# Buck_scetch.net
KiCad netlist of a schematic drawn in EAGLE
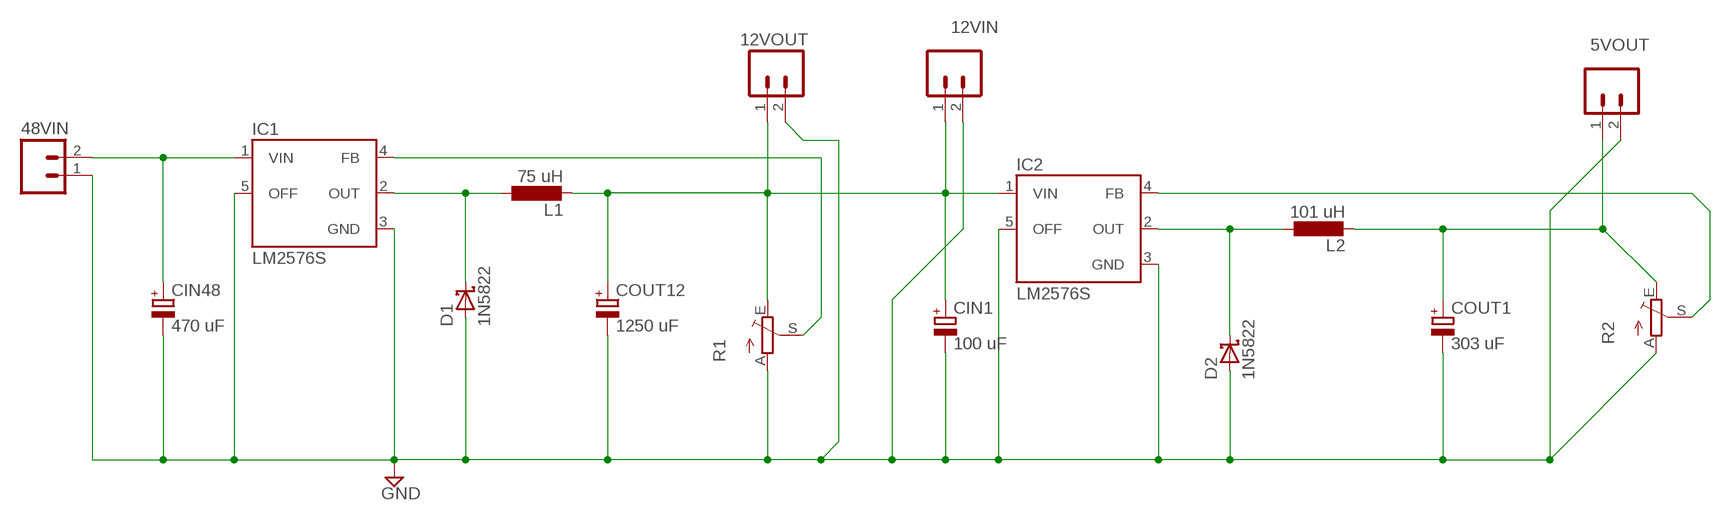
[diagram p0: schematic, sheet 1]

(export (version "E")
  (design (tool "Eeschema 10.0.6"))
  (components
    (comp (ref "5VOUT")
      (value "M02")
      (footprint "eagle-import:02P")
      (libsource (lib "eagle-import") (part "M02"))
    )
    (comp (ref "12VIN")
      (value "M02")
      (footprint "eagle-import:02P")
      (libsource (lib "eagle-import") (part "M02"))
    )
    (comp (ref "12VOUT")
      (value "M02")
      (footprint "eagle-import:02P")
      (libsource (lib "eagle-import") (part "M02"))
    )
    (comp (ref "48VIN")
      (value "M02")
      (footprint "eagle-import:02P")
      (libsource (lib "eagle-import") (part "M02"))
    )
    (comp (ref "CIN1")
      (value "100 uF")
      (footprint "eagle-import:140CLH-0810")
      (libsource (lib "eagle-import") (part "CPOL-EU140CLH-0810"))
    )
    (comp (ref "CIN48")
      (value "470 uF")
      (footprint "eagle-import:140CLH-0810")
      (libsource (lib "eagle-import") (part "CPOL-EU140CLH-0810"))
    )
    (comp (ref "COUT1")
      (value "303 uF")
      (footprint "eagle-import:140CLH-0810")
      (libsource (lib "eagle-import") (part "CPOL-EU140CLH-0810"))
    )
    (comp (ref "COUT12")
      (value "1250 uF")
      (footprint "eagle-import:140CLH-0810")
      (libsource (lib "eagle-import") (part "CPOL-EU140CLH-0810"))
    )
    (comp (ref "D1")
      (value "1N5822")
      (footprint "eagle-import:DIOAD2120W130L950D530P")
      (fields (field (name "MF") "ON Semiconductor"))
      (libsource (lib "eagle-import") (part "1N5822"))
    )
    (comp (ref "D2")
      (value "1N5822")
      (footprint "eagle-import:DIOAD2120W130L950D530P")
      (fields (field (name "MF") "ON Semiconductor"))
      (libsource (lib "eagle-import") (part "1N5822"))
    )
    (comp (ref "IC1")
      (value "LM2576S")
      (footprint "eagle-import:TO263-5")
      (libsource (lib "eagle-import") (part "LM2576S"))
    )
    (comp (ref "IC2")
      (value "LM2576S")
      (footprint "eagle-import:TO263-5")
      (libsource (lib "eagle-import") (part "LM2576S"))
    )
    (comp (ref "L1")
      (value "75 uH")
      (footprint "eagle-import:POWER-CHOKE_WE-TPC")
      (libsource (lib "eagle-import") (part "L-EUWE-TPC"))
    )
    (comp (ref "L2")
      (value "101 uH")
      (footprint "eagle-import:POWER-CHOKE_WE-TPC")
      (libsource (lib "eagle-import") (part "L-EUWE-TPC"))
    )
    (comp (ref "R1")
      (value "0")
      (footprint "eagle-import:B25P")
      (libsource (lib "eagle-import") (part "TRIM_EU-B25P"))
    )
    (comp (ref "R2")
      (value "TRIM_EU-B25P")
      (footprint "eagle-import:B25P")
      (libsource (lib "eagle-import") (part "TRIM_EU-B25P"))
    )
  )
  (nets
    (net (code "1") (name "GND") (class "Default")
      (node (ref "12VIN") (pin "2") (pinfunction "2_2") (pintype "passive"))
      (node (ref "12VOUT") (pin "2") (pinfunction "2_2") (pintype "passive"))
      (node (ref "48VIN") (pin "1") (pinfunction "1_1") (pintype "passive"))
      (node (ref "5VOUT") (pin "2") (pinfunction "2_2") (pintype "passive"))
      (node (ref "CIN1") (pin "-") (pinfunction "-_-") (pintype "passive"))
      (node (ref "CIN48") (pin "-") (pinfunction "-_-") (pintype "passive"))
      (node (ref "COUT1") (pin "-") (pinfunction "-_-") (pintype "passive"))
      (node (ref "COUT12") (pin "-") (pinfunction "-_-") (pintype "passive"))
      (node (ref "D1") (pin "A") (pinfunction "A_A") (pintype "passive"))
      (node (ref "D2") (pin "A") (pinfunction "A_A") (pintype "passive"))
      (node (ref "IC1") (pin "3") (pinfunction "GND_3") (pintype "power_in"))
      (node (ref "IC1") (pin "5") (pinfunction "OFF_5") (pintype "input"))
      (node (ref "IC2") (pin "3") (pinfunction "GND_3") (pintype "power_in"))
      (node (ref "IC2") (pin "5") (pinfunction "OFF_5") (pintype "input"))
      (node (ref "R1") (pin "A") (pinfunction "A_A") (pintype "passive"))
      (node (ref "R2") (pin "A") (pinfunction "A_A") (pintype "passive"))
    )
    (net (code "2") (name "Net-(5VOUT-Pad1)") (class "Default")
      (node (ref "5VOUT") (pin "1") (pinfunction "1_1") (pintype "passive"))
      (node (ref "COUT1") (pin "+") (pinfunction "+_+") (pintype "passive"))
      (node (ref "L2") (pin "2") (pinfunction "2_2") (pintype "passive"))
      (node (ref "R2") (pin "E") (pinfunction "E_E") (pintype "passive"))
    )
    (net (code "3") (name "Net-(IC1-FB)") (class "Default")
      (node (ref "IC1") (pin "4") (pinfunction "FB_4") (pintype "input"))
      (node (ref "R1") (pin "S") (pinfunction "S_S") (pintype "passive"))
    )
    (net (code "4") (name "Net-(IC1-OUT)") (class "Default")
      (node (ref "D1") (pin "C") (pinfunction "C_C") (pintype "passive"))
      (node (ref "IC1") (pin "2") (pinfunction "OUT_2") (pintype "output"))
      (node (ref "L1") (pin "1") (pinfunction "1_1") (pintype "passive"))
    )
    (net (code "5") (name "Net-(IC1-VIN)") (class "Default")
      (node (ref "48VIN") (pin "2") (pinfunction "2_2") (pintype "passive"))
      (node (ref "CIN48") (pin "+") (pinfunction "+_+") (pintype "passive"))
      (node (ref "IC1") (pin "1") (pinfunction "VIN_1") (pintype "power_in"))
    )
    (net (code "6") (name "Net-(IC2-FB)") (class "Default")
      (node (ref "IC2") (pin "4") (pinfunction "FB_4") (pintype "input"))
      (node (ref "R2") (pin "S") (pinfunction "S_S") (pintype "passive"))
    )
    (net (code "7") (name "Net-(IC2-OUT)") (class "Default")
      (node (ref "D2") (pin "C") (pinfunction "C_C") (pintype "passive"))
      (node (ref "IC2") (pin "2") (pinfunction "OUT_2") (pintype "output"))
      (node (ref "L2") (pin "1") (pinfunction "1_1") (pintype "passive"))
    )
    (net (code "8") (name "Net-(IC2-VIN)") (class "Default")
      (node (ref "12VIN") (pin "1") (pinfunction "1_1") (pintype "passive"))
      (node (ref "12VOUT") (pin "1") (pinfunction "1_1") (pintype "passive"))
      (node (ref "CIN1") (pin "+") (pinfunction "+_+") (pintype "passive"))
      (node (ref "COUT12") (pin "+") (pinfunction "+_+") (pintype "passive"))
      (node (ref "IC2") (pin "1") (pinfunction "VIN_1") (pintype "power_in"))
      (node (ref "L1") (pin "2") (pinfunction "2_2") (pintype "passive"))
      (node (ref "R1") (pin "E") (pinfunction "E_E") (pintype "passive"))
    )
  )
)
